# Power-Tree-Main.net
KiCad netlist of a schematic drawn in Altium Designer
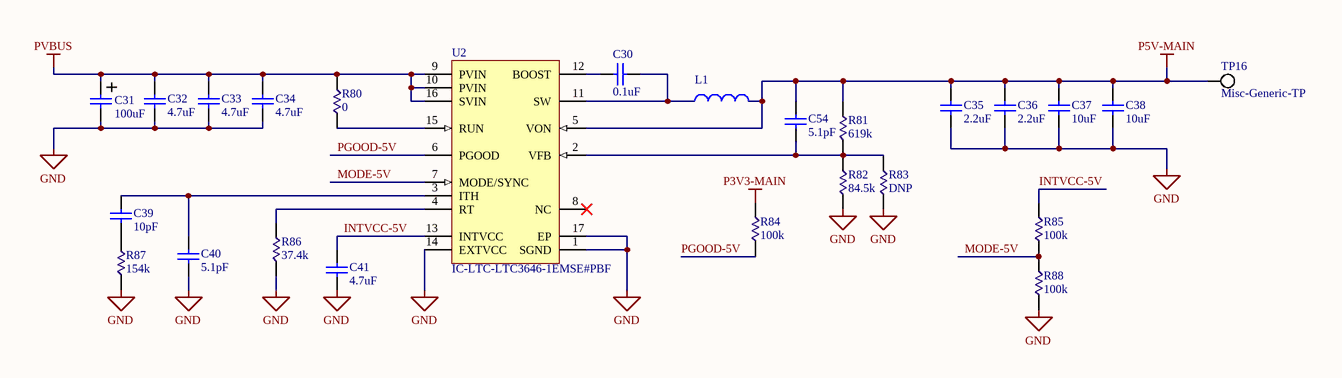
[diagram p0: Power-Tree-Main.SchDoc]

(export (version "E")
  (design (tool "Eeschema 10.0.6"))
  (components
    (comp (ref "C30")
      (value "0.1uF")
      (footprint "FOOTPRINT-0805-GEN")
      (description "Capacitor")
      (fields (field (name "Comment") "Capacitor-Generic-0805") (field (name "PUBLISHER") "Altium Limited"))
      (libsource (lib "HR-Master-Integrated") (part "Capacitor-Generic-0805"))
    )
    (comp (ref "C31")
      (value "100uF")
      (footprint "FOOTPRINT-NIPPON-JA0")
      (description "CAP ALUM POLY 100UF 20% 50V SMD")
      (fields (field (name "Comment") "Capacitor-Nippon-HHXC350ARA470MF80G"))
      (libsource (lib "HR-Master-Integrated") (part "Capacitor-Nippon-HHXC350ARA470MF80G"))
    )
    (comp (ref "C32")
      (value "4.7uF")
      (footprint "FOOTPRINT-1206-GEN")
      (description "CAP CER 1206 4.7UF 50V X7R 10%")
      (fields (field (name "Comment") "C1206C475K5RACAUTO") (field (name "PUBLISHER") "Altium Limited"))
      (libsource (lib "HR-Master-Integrated") (part "Capacitor-Generic-1206"))
    )
    (comp (ref "C33")
      (value "4.7uF")
      (footprint "FOOTPRINT-1206-GEN")
      (description "CAP CER 1206 4.7UF 50V X7R 10%")
      (fields (field (name "Comment") "C1206C475K5RACAUTO") (field (name "PUBLISHER") "Altium Limited"))
      (libsource (lib "HR-Master-Integrated") (part "Capacitor-Generic-1206"))
    )
    (comp (ref "C34")
      (value "4.7uF")
      (footprint "FOOTPRINT-1206-GEN")
      (description "CAP CER 1206 4.7UF 50V X7R 10%")
      (fields (field (name "Comment") "C1206C475K5RACAUTO") (field (name "PUBLISHER") "Altium Limited"))
      (libsource (lib "HR-Master-Integrated") (part "Capacitor-Generic-1206"))
    )
    (comp (ref "C35")
      (value "2.2uF")
      (footprint "FOOTPRINT-0805-GEN")
      (description "CAP CER 2.2UF 10V X5R 0805")
      (fields (field (name "Comment") "C0805C225K8PAC") (field (name "PUBLISHER") "Altium Limited"))
      (libsource (lib "HR-Master-Integrated") (part "Capacitor-Generic-0805"))
    )
    (comp (ref "C36")
      (value "2.2uF")
      (footprint "FOOTPRINT-0805-GEN")
      (description "CAP CER 2.2UF 10V X5R 0805")
      (fields (field (name "Comment") "C0805C225K8PAC") (field (name "PUBLISHER") "Altium Limited"))
      (libsource (lib "HR-Master-Integrated") (part "Capacitor-Generic-0805"))
    )
    (comp (ref "C37")
      (value "10uF")
      (footprint "FOOTPRINT-0805-GEN")
      (description "CAP CER 10UF 10V X5R 0805")
      (fields (field (name "Comment") "C0805C106K8PAC") (field (name "PUBLISHER") "Altium Limited"))
      (libsource (lib "HR-Master-Integrated") (part "Capacitor-Generic-0805"))
    )
    (comp (ref "C38")
      (value "10uF")
      (footprint "FOOTPRINT-0805-GEN")
      (description "CAP CER 10UF 10V X5R 0805")
      (fields (field (name "Comment") "C0805C106K8PAC") (field (name "PUBLISHER") "Altium Limited"))
      (libsource (lib "HR-Master-Integrated") (part "Capacitor-Generic-0805"))
    )
    (comp (ref "C39")
      (value "10pF")
      (footprint "FOOTPRINT-0805-GEN")
      (description "CAP CER 0805 10PF 25V ULTRA STAB")
      (fields (field (name "Comment") "C0805C100J3HACTU") (field (name "PUBLISHER") "Altium Limited"))
      (libsource (lib "HR-Master-Integrated") (part "Capacitor-Generic-0805"))
    )
    (comp (ref "C40")
      (value "5.1pF")
      (footprint "FOOTPRINT-0805-GEN")
      (description "Capacitor")
      (fields (field (name "Comment") "C0805C519K5GACTU") (field (name "PUBLISHER") "Altium Limited"))
      (libsource (lib "HR-Master-Integrated") (part "Capacitor-Generic-0805"))
    )
    (comp (ref "C41")
      (value "4.7uF")
      (footprint "FOOTPRINT-0805-GEN")
      (description "CAP CER 4.7UF 10V X5R 0805")
      (fields (field (name "Comment") "C0805C475K8PAC") (field (name "PUBLISHER") "Altium Limited"))
      (libsource (lib "HR-Master-Integrated") (part "Capacitor-Generic-0805"))
    )
    (comp (ref "C54")
      (value "5.1pF")
      (footprint "FOOTPRINT-0805-GEN")
      (description "Capacitor")
      (fields (field (name "Comment") "C0805C519K5GACTU") (field (name "PUBLISHER") "Altium Limited"))
      (libsource (lib "HR-Master-Integrated") (part "Capacitor-Generic-0805"))
    )
    (comp (ref "L1")
      (value "Inductor-Bourns-SRP7050TA-2R2M")
      (footprint "FOOTPRINT-BOURNS-SRP7050TA")
      (description "FIXED IND 2.2UH 10A 12 MOHM SMD")
      (libsource (lib "HR-Master-Integrated") (part "Inductor-Bourns-SRP7050TA-2R2M"))
    )
    (comp (ref "R80")
      (value "0")
      (footprint "FOOTPRINT-0805-GEN")
      (description "1/8 Watt Surface Mount Resistor")
      (fields (field (name "Comment") "SMC"))
      (libsource (lib "HR-Master-Integrated") (part "Resistor-Generic-0805-2012"))
    )
    (comp (ref "R81")
      (value "619k")
      (footprint "FOOTPRINT-0805-GEN")
      (description "1/8 Watt Surface Mount Resistor")
      (fields (field (name "Comment") "SMC"))
      (libsource (lib "HR-Master-Integrated") (part "Resistor-Generic-0805-2012"))
    )
    (comp (ref "R82")
      (value "84.5k")
      (footprint "FOOTPRINT-0805-GEN")
      (description "1/8 Watt Surface Mount Resistor")
      (fields (field (name "Comment") "SMC"))
      (libsource (lib "HR-Master-Integrated") (part "Resistor-Generic-0805-2012"))
    )
    (comp (ref "R83")
      (value "DNP")
      (footprint "FOOTPRINT-0805-GEN")
      (description "1/8 Watt Surface Mount Resistor")
      (fields (field (name "Comment") "Trim, 0 ohm"))
      (libsource (lib "HR-Master-Integrated") (part "Resistor-Generic-0805-2012"))
    )
    (comp (ref "R84")
      (value "100k")
      (footprint "FOOTPRINT-0805-GEN")
      (description "1/8 Watt Surface Mount Resistor")
      (fields (field (name "Comment") "SMC"))
      (libsource (lib "HR-Master-Integrated") (part "Resistor-Generic-0805-2012"))
    )
    (comp (ref "R85")
      (value "100k")
      (footprint "FOOTPRINT-0805-GEN")
      (description "1/8 Watt Surface Mount Resistor")
      (fields (field (name "Comment") "SMC"))
      (libsource (lib "HR-Master-Integrated") (part "Resistor-Generic-0805-2012"))
    )
    (comp (ref "R86")
      (value "37.4k")
      (footprint "FOOTPRINT-0805-GEN")
      (description "1/8 Watt Surface Mount Resistor")
      (fields (field (name "Comment") "SMC"))
      (libsource (lib "HR-Master-Integrated") (part "Resistor-Generic-0805-2012"))
    )
    (comp (ref "R87")
      (value "154k")
      (footprint "FOOTPRINT-0805-GEN")
      (description "1/8 Watt Surface Mount Resistor")
      (fields (field (name "Comment") "SMC"))
      (libsource (lib "HR-Master-Integrated") (part "Resistor-Generic-0805-2012"))
    )
    (comp (ref "R88")
      (value "100k")
      (footprint "FOOTPRINT-0805-GEN")
      (description "1/8 Watt Surface Mount Resistor")
      (fields (field (name "Comment") "SMC"))
      (libsource (lib "HR-Master-Integrated") (part "Resistor-Generic-0805-2012"))
    )
    (comp (ref "TP16")
      (value "Misc-Generic-TP")
      (footprint "FOOTPRINT-GENERIC-TP-VIA-1MM5")
      (libsource (lib "HR-Master-Integrated") (part "Misc-Generic-TP"))
    )
    (comp (ref "U2")
      (value "IC-LTC-LTC3646-1EMSE#PBF")
      (footprint "FOOTPRINT-LTC-LTC3646")
      (description "1 A Synchronous Step-Down Converter, 16-pin SOP (MSE-16-EDP), -40 to 85 degC, Pb-Free")
      (fields (field (name "PARTNUMBER") "LTC3646EMSE#PBF") (field (name "MANUFACTURER") "Linear Technology"))
      (libsource (lib "HR-Master-Integrated") (part "IC-LTC-LTC3646-1EMSE#PBF"))
    )
  )
  (nets
    (net (code "1") (name "/INTVCC-5V") (class "Default")
      (node (ref "C41") (pin "2") (pinfunction "2_2") (pintype "passive"))
      (node (ref "R85") (pin "2") (pinfunction "2_2") (pintype "passive"))
      (node (ref "U2") (pin "13") (pinfunction "INTVCC_13") (pintype "power_in"))
    )
    (net (code "2") (name "/MODE-5V") (class "Default")
      (node (ref "R85") (pin "1") (pinfunction "1_1") (pintype "passive"))
      (node (ref "R88") (pin "2") (pinfunction "2_2") (pintype "passive"))
      (node (ref "U2") (pin "7") (pinfunction "MODE/SYNC_7") (pintype "input"))
    )
    (net (code "3") (name "/PGOOD-5V") (class "Default")
      (node (ref "R84") (pin "1") (pinfunction "1_1") (pintype "passive"))
      (node (ref "U2") (pin "6") (pinfunction "PGOOD_6") (pintype "tri_state"))
    )
    (net (code "4") (name "GND") (class "Default")
      (node (ref "C31") (pin "2") (pinfunction "2_2") (pintype "passive"))
      (node (ref "C32") (pin "1") (pinfunction "1_1") (pintype "passive"))
      (node (ref "C33") (pin "1") (pinfunction "1_1") (pintype "passive"))
      (node (ref "C34") (pin "1") (pinfunction "1_1") (pintype "passive"))
      (node (ref "C35") (pin "2") (pinfunction "2_2") (pintype "passive"))
      (node (ref "C36") (pin "2") (pinfunction "2_2") (pintype "passive"))
      (node (ref "C37") (pin "1") (pinfunction "1_1") (pintype "passive"))
      (node (ref "C38") (pin "1") (pinfunction "1_1") (pintype "passive"))
      (node (ref "C40") (pin "1") (pinfunction "1_1") (pintype "passive"))
      (node (ref "C41") (pin "1") (pinfunction "1_1") (pintype "passive"))
      (node (ref "R82") (pin "2") (pinfunction "2_2") (pintype "passive"))
      (node (ref "R83") (pin "2") (pinfunction "2_2") (pintype "passive"))
      (node (ref "R86") (pin "1") (pinfunction "1_1") (pintype "passive"))
      (node (ref "R87") (pin "1") (pinfunction "1_1") (pintype "passive"))
      (node (ref "R88") (pin "1") (pinfunction "1_1") (pintype "passive"))
      (node (ref "U2") (pin "1") (pinfunction "SGND_1") (pintype "power_in"))
      (node (ref "U2") (pin "14") (pinfunction "EXTVCC_14") (pintype "power_in"))
      (node (ref "U2") (pin "17") (pinfunction "EP_17") (pintype "power_in"))
    )
    (net (code "5") (name "Net-(C39-Pad1)") (class "Default")
      (node (ref "C39") (pin "1") (pinfunction "1_1") (pintype "passive"))
      (node (ref "R87") (pin "2") (pinfunction "2_2") (pintype "passive"))
    )
    (net (code "6") (name "Net-(U2-BOOST)") (class "Default")
      (node (ref "C30") (pin "2") (pinfunction "2_2") (pintype "passive"))
      (node (ref "U2") (pin "12") (pinfunction "BOOST_12") (pintype "passive"))
    )
    (net (code "7") (name "Net-(U2-ITH)") (class "Default")
      (node (ref "C39") (pin "2") (pinfunction "2_2") (pintype "passive"))
      (node (ref "C40") (pin "2") (pinfunction "2_2") (pintype "passive"))
      (node (ref "U2") (pin "3") (pinfunction "ITH_3") (pintype "passive"))
    )
    (net (code "8") (name "Net-(U2-RT)") (class "Default")
      (node (ref "R86") (pin "2") (pinfunction "2_2") (pintype "passive"))
      (node (ref "U2") (pin "4") (pinfunction "RT_4") (pintype "passive"))
    )
    (net (code "9") (name "Net-(U2-RUN)") (class "Default")
      (node (ref "R80") (pin "2") (pinfunction "2_2") (pintype "passive"))
      (node (ref "U2") (pin "15") (pinfunction "RUN_15") (pintype "input"))
    )
    (net (code "10") (name "Net-(U2-SW)") (class "Default")
      (node (ref "C30") (pin "1") (pinfunction "1_1") (pintype "passive"))
      (node (ref "L1") (pin "1") (pinfunction "1_1") (pintype "passive"))
      (node (ref "U2") (pin "11") (pinfunction "SW_11") (pintype "power_in"))
    )
    (net (code "11") (name "Net-(U2-VFB)") (class "Default")
      (node (ref "C54") (pin "1") (pinfunction "1_1") (pintype "passive"))
      (node (ref "R81") (pin "1") (pinfunction "1_1") (pintype "passive"))
      (node (ref "R82") (pin "1") (pinfunction "1_1") (pintype "passive"))
      (node (ref "R83") (pin "1") (pinfunction "1_1") (pintype "passive"))
      (node (ref "U2") (pin "2") (pinfunction "VFB_2") (pintype "input"))
    )
    (net (code "12") (name "P3V3-MAIN") (class "Default")
      (node (ref "R84") (pin "2") (pinfunction "2_2") (pintype "passive"))
    )
    (net (code "13") (name "P5V-MAIN") (class "Default")
      (node (ref "C35") (pin "1") (pinfunction "1_1") (pintype "passive"))
      (node (ref "C36") (pin "1") (pinfunction "1_1") (pintype "passive"))
      (node (ref "C37") (pin "2") (pinfunction "2_2") (pintype "passive"))
      (node (ref "C38") (pin "2") (pinfunction "2_2") (pintype "passive"))
      (node (ref "C54") (pin "2") (pinfunction "2_2") (pintype "passive"))
      (node (ref "L1") (pin "2") (pinfunction "2_2") (pintype "passive"))
      (node (ref "R81") (pin "2") (pinfunction "2_2") (pintype "passive"))
      (node (ref "TP16") (pin "1") (pinfunction "TP_1") (pintype "passive"))
      (node (ref "U2") (pin "5") (pinfunction "VON_5") (pintype "input"))
    )
    (net (code "14") (name "PVBUS") (class "Default")
      (node (ref "C31") (pin "1") (pinfunction "1_1") (pintype "passive"))
      (node (ref "C32") (pin "2") (pinfunction "2_2") (pintype "passive"))
      (node (ref "C33") (pin "2") (pinfunction "2_2") (pintype "passive"))
      (node (ref "C34") (pin "2") (pinfunction "2_2") (pintype "passive"))
      (node (ref "R80") (pin "1") (pinfunction "1_1") (pintype "passive"))
      (node (ref "U2") (pin "10") (pinfunction "PVIN_10") (pintype "power_in"))
      (node (ref "U2") (pin "16") (pinfunction "SVIN_16") (pintype "power_in"))
      (node (ref "U2") (pin "9") (pinfunction "PVIN_9") (pintype "power_in"))
    )
    (net (code "15") (name "unconnected-(U2-NC-Pad8)") (class "Default")
      (node (ref "U2") (pin "8") (pinfunction "NC_8") (pintype "passive+no_connect"))
    )
  )
)
